# 467999_001_3_3.net
KiCad netlist of a schematic drawn in Altium Designer
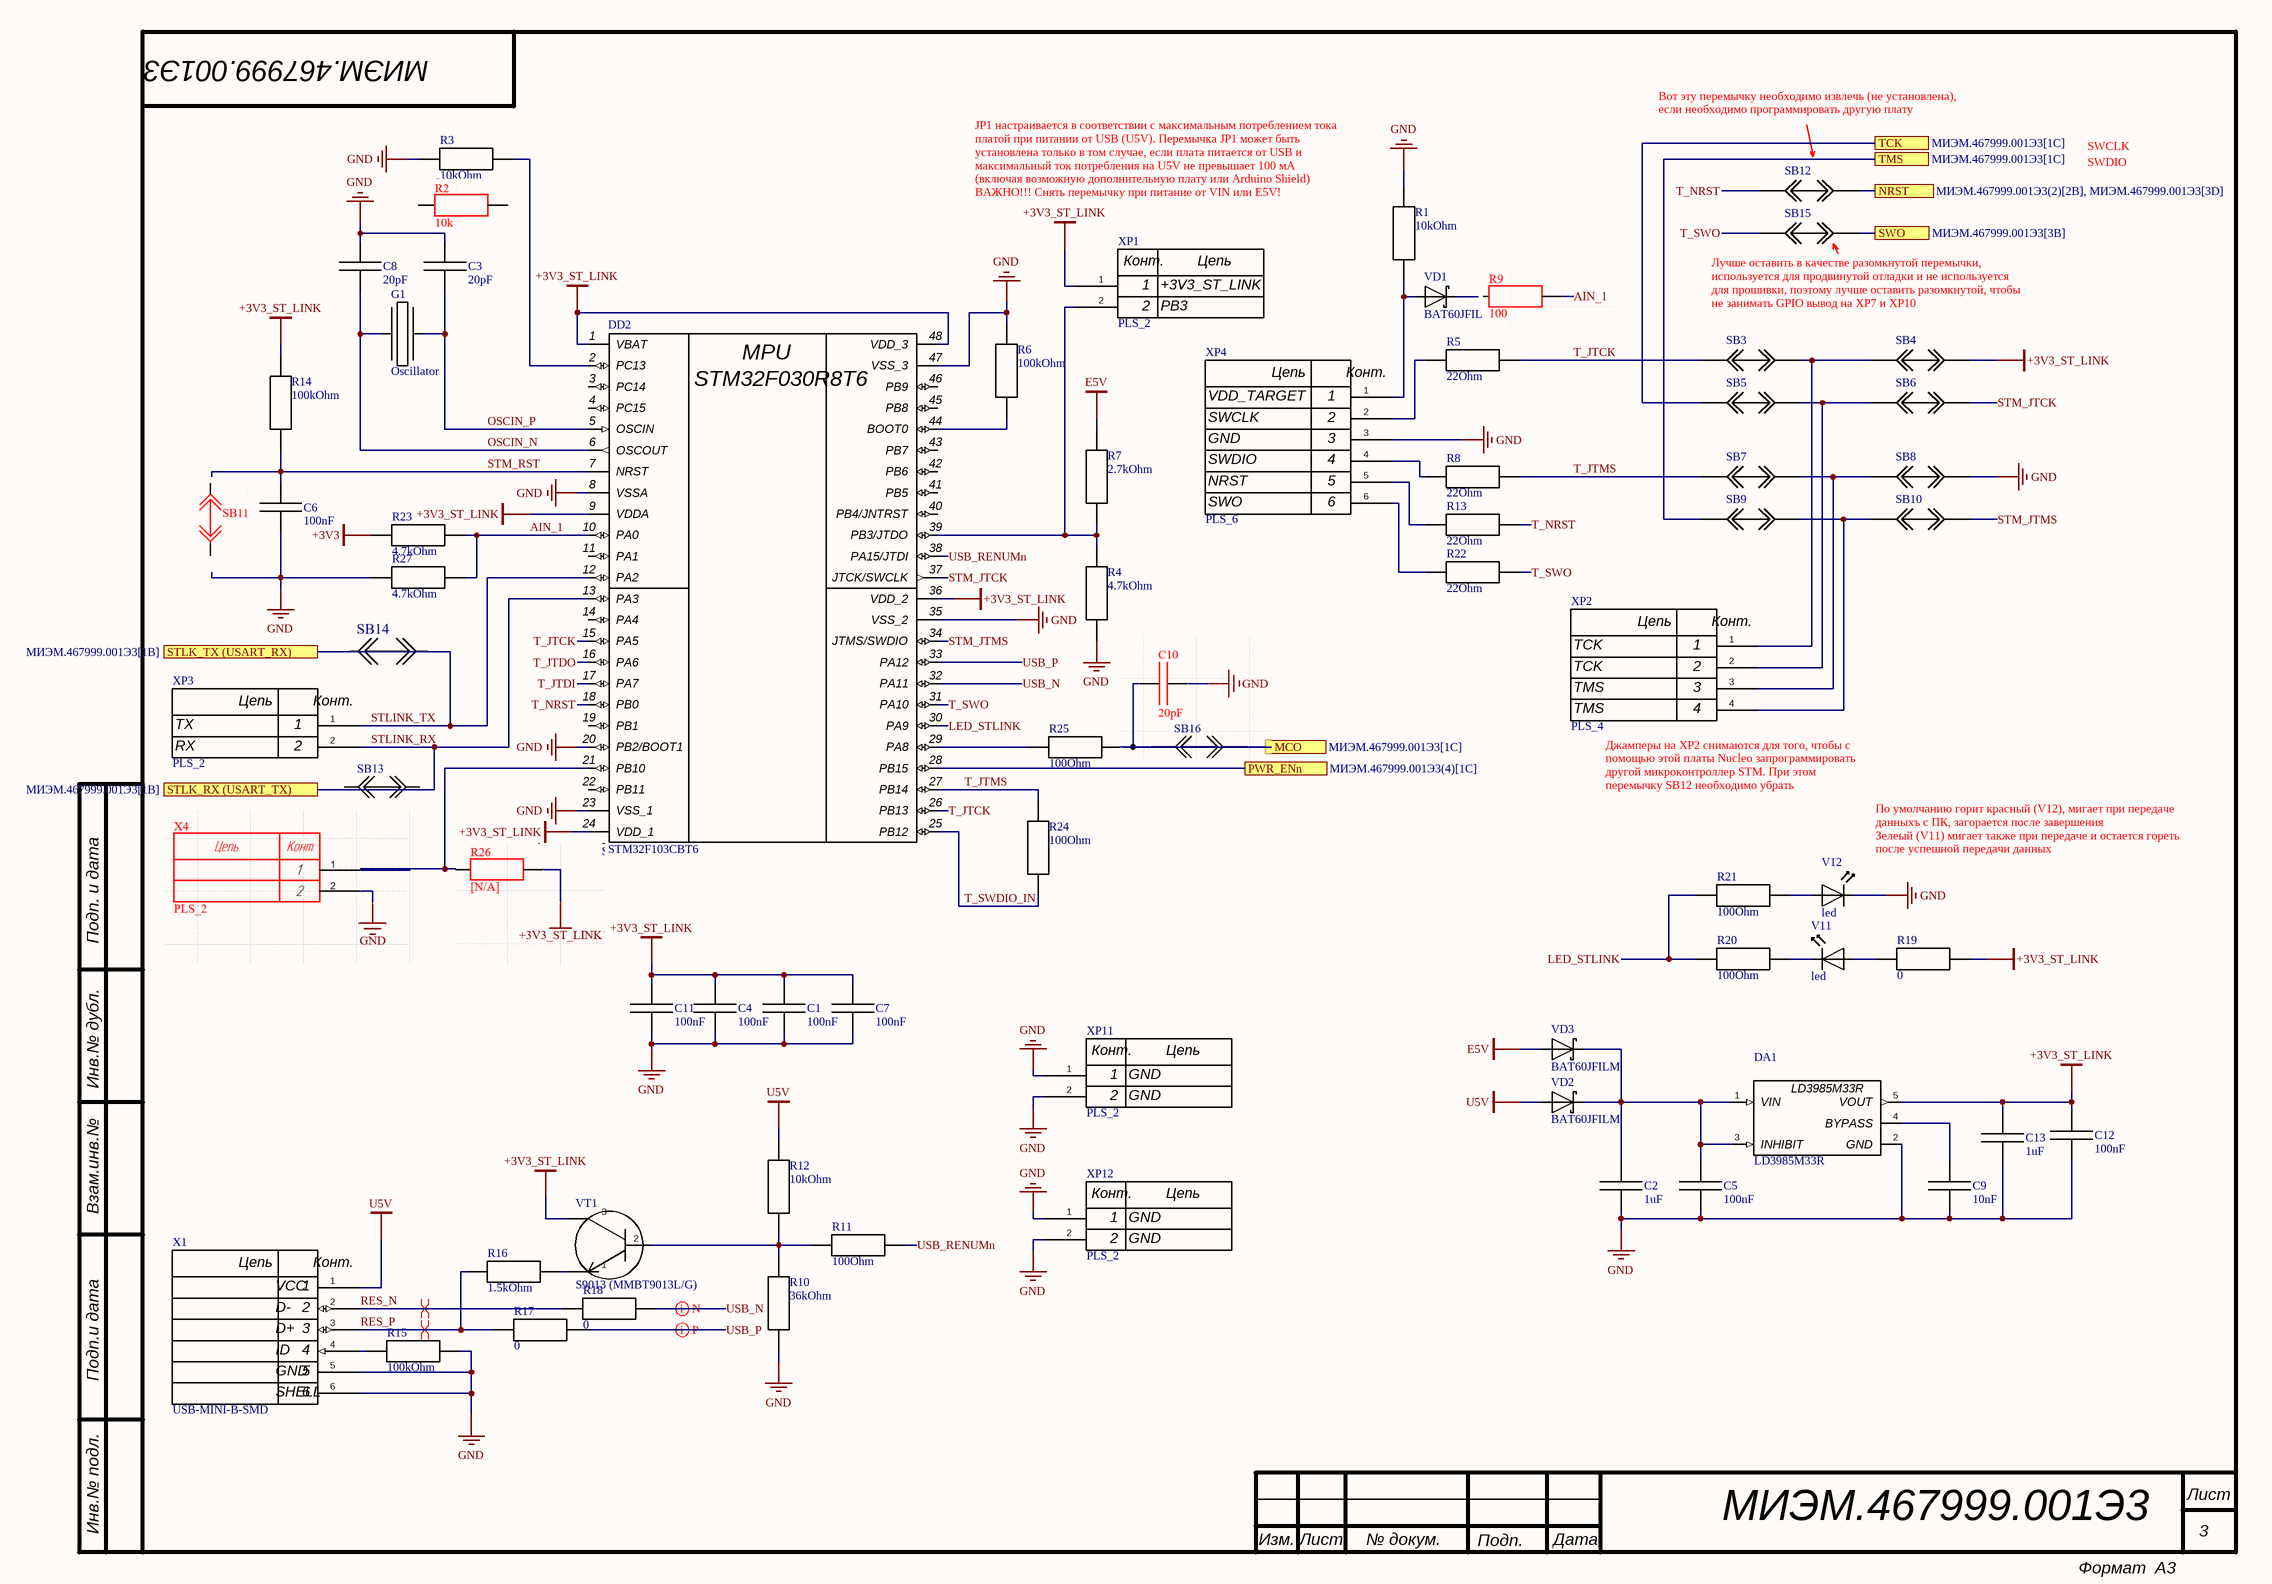
[diagram p0: МИЭМ.467999.001Э3(3).SchDoc]

(export (version "E")
  (design (tool "Eeschema 10.0.6"))
  (components
    (comp (ref "C1")
      (value "100nF")
      (footprint "0603")
      (fields
        (field (name "TOLERANCE") "10%")
        (field (name "PARTNUMBER") "CC0603KRX7R0BB104")
        (field (name "MANUFACTURER") "Yageo")
      )
      (libsource (lib "Capacitor_GOST") (part "Сapacitor"))
    )
    (comp (ref "C2")
      (value "1uF")
      (footprint "0603")
      (fields
        (field (name "TOLERANCE") "10%")
        (field (name "PARTNUMBER") "GRM185R61A105K")
        (field (name "MANUFACTURER") "Murata Electronics")
      )
      (libsource (lib "Capacitor_GOST") (part "Сapacitor"))
    )
    (comp (ref "C3")
      (value "20pF")
      (footprint "0603")
      (fields
        (field (name "TOLERANCE") "5%")
        (field (name "PARTNUMBER") "GRM1885C1H200J")
        (field (name "MANUFACTURER") "Murata Electronics")
      )
      (libsource (lib "Capacitor_GOST") (part "Сapacitor"))
    )
    (comp (ref "C4")
      (value "100nF")
      (footprint "0603")
      (fields
        (field (name "TOLERANCE") "10%")
        (field (name "PARTNUMBER") "CC0603KRX7R0BB104")
        (field (name "MANUFACTURER") "Yageo")
      )
      (libsource (lib "Capacitor_GOST") (part "Сapacitor"))
    )
    (comp (ref "C5")
      (value "100nF")
      (footprint "0603")
      (fields
        (field (name "TOLERANCE") "10%")
        (field (name "PARTNUMBER") "CC0603KRX7R0BB104")
        (field (name "MANUFACTURER") "Yageo")
      )
      (libsource (lib "Capacitor_GOST") (part "Сapacitor"))
    )
    (comp (ref "C6")
      (value "100nF")
      (footprint "0603")
      (fields
        (field (name "TOLERANCE") "10%")
        (field (name "PARTNUMBER") "CC0603KRX7R0BB104")
        (field (name "MANUFACTURER") "Yageo")
      )
      (libsource (lib "Capacitor_GOST") (part "Сapacitor"))
    )
    (comp (ref "C7")
      (value "100nF")
      (footprint "0603")
      (fields
        (field (name "TOLERANCE") "10%")
        (field (name "PARTNUMBER") "CC0603KRX7R0BB104")
        (field (name "MANUFACTURER") "Yageo")
      )
      (libsource (lib "Capacitor_GOST") (part "Сapacitor"))
    )
    (comp (ref "C8")
      (value "20pF")
      (footprint "0603")
      (fields
        (field (name "TOLERANCE") "5%")
        (field (name "PARTNUMBER") "GRM1885C1H200J")
        (field (name "MANUFACTURER") "Murata Electronics")
      )
      (libsource (lib "Capacitor_GOST") (part "Сapacitor"))
    )
    (comp (ref "C9")
      (value "10nF")
      (footprint "0603")
      (fields
        (field (name "TOLERANCE") "10%")
        (field (name "PARTNUMBER") "CC0603KRX7R0BB103")
        (field (name "MANUFACTURER") "Yageo")
      )
      (libsource (lib "Capacitor_GOST") (part "Сapacitor"))
    )
    (comp (ref "C11")
      (value "100nF")
      (footprint "0603")
      (fields
        (field (name "TOLERANCE") "10%")
        (field (name "PARTNUMBER") "CC0603KRX7R0BB104")
        (field (name "MANUFACTURER") "Yageo")
      )
      (libsource (lib "Capacitor_GOST") (part "Сapacitor"))
    )
    (comp (ref "C12")
      (value "100nF")
      (footprint "0603")
      (fields
        (field (name "TOLERANCE") "10%")
        (field (name "PARTNUMBER") "CC0603KRX7R0BB104")
        (field (name "MANUFACTURER") "Yageo")
      )
      (libsource (lib "Capacitor_GOST") (part "Сapacitor"))
    )
    (comp (ref "C13")
      (value "1uF")
      (footprint "0603")
      (fields
        (field (name "TOLERANCE") "10%")
        (field (name "PARTNUMBER") "GRM185R61A105K")
        (field (name "MANUFACTURER") "Murata Electronics")
      )
      (libsource (lib "Capacitor_GOST") (part "Сapacitor"))
    )
    (comp (ref "DA1")
      (value "LD3985M33R")
      (footprint "LD3985M33R (SOT-23-5)")
      (fields (field (name "MANUFACTURER") "STMicroelectronics"))
      (libsource (lib "ICs_GOST") (part "LD3985M33R"))
    )
    (comp (ref "DD2")
      (value "STM32F103CBT6")
      (footprint "LQFP48-7x7mm")
      (fields (field (name "MANUFACTURER") "STMicroelectronics"))
      (libsource (lib "STM_GOST") (part "STM32F103CBT6"))
    )
    (comp (ref "G1")
      (value "Oscillator")
      (footprint "HC49SMD")
      (libsource (lib "Oscillator_GOST") (part "Oscillator"))
    )
    (comp (ref "R1")
      (value "10kOhm")
      (footprint "0603")
      (fields
        (field (name "POWER") "0.1Вт")
        (field (name "TOLERANCE") "1%")
        (field (name "PARTNUMBER") "RC0603FR-0710KL")
      )
      (libsource (lib "") (part "Resistor_1"))
    )
    (comp (ref "R3")
      (value "10kOhm")
      (footprint "0603")
      (fields
        (field (name "POWER") "0.1Вт")
        (field (name "TOLERANCE") "1%")
        (field (name "PARTNUMBER") "RC0603FR-0710KL")
      )
      (libsource (lib "Resistor_GOST") (part "Resistor"))
    )
    (comp (ref "R4")
      (value "4.7kOhm")
      (footprint "0603")
      (fields
        (field (name "POWER") "0.1Вт")
        (field (name "TOLERANCE") "5%")
        (field (name "PARTNUMBER") "RC0603JR-074K7L")
      )
      (libsource (lib "") (part "Resistor_3"))
    )
    (comp (ref "R5")
      (value "22Ohm")
      (footprint "0603")
      (fields
        (field (name "POWER") "0.1Вт")
        (field (name "TOLERANCE") "1%")
        (field (name "PARTNUMBER") "RC0603FR-0722RL")
      )
      (libsource (lib "") (part "Resistor_2"))
    )
    (comp (ref "R6")
      (value "100kOhm")
      (footprint "0603")
      (fields
        (field (name "POWER") "0.1Вт")
        (field (name "TOLERANCE") "1%")
        (field (name "PARTNUMBER") "0603WAF1003T5E")
      )
      (libsource (lib "") (part "Resistor_3"))
    )
    (comp (ref "R7")
      (value "2.7kOhm")
      (footprint "0603")
      (fields
        (field (name "POWER") "0.1Вт")
        (field (name "TOLERANCE") "5%")
        (field (name "PARTNUMBER") "RC0603JR-072K7L")
      )
      (libsource (lib "") (part "Resistor_3"))
    )
    (comp (ref "R8")
      (value "22Ohm")
      (footprint "0603")
      (fields
        (field (name "POWER") "0.1Вт")
        (field (name "TOLERANCE") "1%")
        (field (name "PARTNUMBER") "RC0603FR-0722RL")
      )
      (libsource (lib "") (part "Resistor_2"))
    )
    (comp (ref "R10")
      (value "36kOhm")
      (footprint "0603")
      (fields
        (field (name "POWER") "0.1Вт")
        (field (name "TOLERANCE") "5%")
        (field (name "PARTNUMBER") "RC0603JR-0736KL")
      )
      (libsource (lib "") (part "Resistor_3"))
    )
    (comp (ref "R11")
      (value "100Ohm")
      (footprint "0603")
      (fields
        (field (name "POWER") "0.1Вт")
        (field (name "TOLERANCE") "1%")
        (field (name "PARTNUMBER") "AC0603FR-07100RL")
      )
      (libsource (lib "") (part "Resistor_2"))
    )
    (comp (ref "R12")
      (value "10kOhm")
      (footprint "0603")
      (fields
        (field (name "POWER") "0.1Вт")
        (field (name "TOLERANCE") "1%")
        (field (name "PARTNUMBER") "RC0603FR-0710KL")
      )
      (libsource (lib "") (part "Resistor_3"))
    )
    (comp (ref "R13")
      (value "22Ohm")
      (footprint "0603")
      (fields
        (field (name "POWER") "0.1Вт")
        (field (name "TOLERANCE") "1%")
        (field (name "PARTNUMBER") "RC0603FR-0722RL")
      )
      (libsource (lib "") (part "Resistor_2"))
    )
    (comp (ref "R14")
      (value "100kOhm")
      (footprint "0603")
      (fields
        (field (name "POWER") "0.1Вт")
        (field (name "TOLERANCE") "1%")
        (field (name "PARTNUMBER") "0603WAF1003T5E")
      )
      (libsource (lib "") (part "Resistor_3"))
    )
    (comp (ref "R15")
      (value "100kOhm")
      (footprint "0603")
      (fields
        (field (name "POWER") "0.1Вт")
        (field (name "TOLERANCE") "1%")
        (field (name "PARTNUMBER") "0603WAF1003T5E")
      )
      (libsource (lib "Resistor_GOST") (part "Resistor"))
    )
    (comp (ref "R16")
      (value "1.5kOhm")
      (footprint "0603")
      (fields
        (field (name "POWER") "0.1Вт")
        (field (name "TOLERANCE") "1%")
        (field (name "PARTNUMBER") "RC0603FR-071K5L")
      )
      (libsource (lib "Resistor_GOST") (part "Resistor"))
    )
    (comp (ref "R17")
      (value "0")
      (footprint "0603")
      (fields
        (field (name "POWER") "0.1Вт")
        (field (name "TOLERANCE") "1%")
        (field (name "PARTNUMBER") "RC0603FR-070RL")
      )
      (libsource (lib "Resistor_GOST") (part "Resistor"))
    )
    (comp (ref "R18")
      (value "0")
      (footprint "0603")
      (fields
        (field (name "POWER") "0.1Вт")
        (field (name "TOLERANCE") "1%")
        (field (name "PARTNUMBER") "RC0603FR-070RL")
      )
      (libsource (lib "Resistor_GOST") (part "Resistor"))
    )
    (comp (ref "R19")
      (value "0")
      (footprint "0603")
      (fields
        (field (name "POWER") "0.1Вт")
        (field (name "TOLERANCE") "1%")
        (field (name "PARTNUMBER") "RC0603FR-070RL")
      )
      (libsource (lib "Resistor_GOST") (part "Resistor"))
    )
    (comp (ref "R20")
      (value "100Ohm")
      (footprint "0603")
      (fields
        (field (name "POWER") "0.1Вт")
        (field (name "TOLERANCE") "1%")
        (field (name "PARTNUMBER") "AC0603FR-07100RL")
      )
      (libsource (lib "Resistor_GOST") (part "Resistor"))
    )
    (comp (ref "R21")
      (value "100Ohm")
      (footprint "0603")
      (fields
        (field (name "POWER") "0.1Вт")
        (field (name "TOLERANCE") "1%")
        (field (name "PARTNUMBER") "AC0603FR-07100RL")
      )
      (libsource (lib "Resistor_GOST") (part "Resistor"))
    )
    (comp (ref "R22")
      (value "22Ohm")
      (footprint "0603")
      (fields
        (field (name "POWER") "0.1Вт")
        (field (name "TOLERANCE") "1%")
        (field (name "PARTNUMBER") "RC0603FR-0722RL")
      )
      (libsource (lib "") (part "Resistor_2"))
    )
    (comp (ref "R23")
      (value "4.7kOhm")
      (footprint "0603")
      (fields
        (field (name "POWER") "0.1Вт")
        (field (name "TOLERANCE") "5%")
        (field (name "PARTNUMBER") "RC0603JR-074K7L")
      )
      (libsource (lib "Resistor_GOST") (part "Resistor"))
    )
    (comp (ref "R24")
      (value "100Ohm")
      (footprint "0603")
      (fields
        (field (name "POWER") "0.1Вт")
        (field (name "TOLERANCE") "1%")
        (field (name "PARTNUMBER") "AC0603FR-07100RL")
      )
      (libsource (lib "") (part "Resistor_3"))
    )
    (comp (ref "R25")
      (value "100Ohm")
      (footprint "0603")
      (fields
        (field (name "POWER") "0.1Вт")
        (field (name "TOLERANCE") "1%")
        (field (name "PARTNUMBER") "AC0603FR-07100RL")
      )
      (libsource (lib "") (part "Resistor_2"))
    )
    (comp (ref "R27")
      (value "4.7kOhm")
      (footprint "0603")
      (fields
        (field (name "POWER") "0.1Вт")
        (field (name "TOLERANCE") "5%")
        (field (name "PARTNUMBER") "RC0603JR-074K7L")
      )
      (libsource (lib "Resistor_GOST") (part "Resistor"))
    )
    (comp (ref "SB3")
      (value "Jumper")
      (footprint "Jumper")
      (libsource (lib "Connector_GOST") (part "Jumper"))
    )
    (comp (ref "SB4")
      (value "Jumper")
      (footprint "Jumper")
      (libsource (lib "Connector_GOST") (part "Jumper"))
    )
    (comp (ref "SB5")
      (value "Jumper")
      (footprint "Jumper")
      (libsource (lib "Connector_GOST") (part "Jumper"))
    )
    (comp (ref "SB6")
      (value "Jumper")
      (footprint "Jumper")
      (libsource (lib "Connector_GOST") (part "Jumper"))
    )
    (comp (ref "SB7")
      (value "Jumper")
      (footprint "Jumper")
      (libsource (lib "Connector_GOST") (part "Jumper"))
    )
    (comp (ref "SB8")
      (value "Jumper")
      (footprint "Jumper")
      (libsource (lib "Connector_GOST") (part "Jumper"))
    )
    (comp (ref "SB9")
      (value "Jumper")
      (footprint "Jumper")
      (libsource (lib "Connector_GOST") (part "Jumper"))
    )
    (comp (ref "SB10")
      (value "Jumper")
      (footprint "Jumper")
      (libsource (lib "Connector_GOST") (part "Jumper"))
    )
    (comp (ref "SB12")
      (value "Jumper")
      (footprint "Jumper")
      (libsource (lib "Connector_GOST") (part "Jumper"))
    )
    (comp (ref "SB15")
      (value "Jumper")
      (footprint "Jumper")
      (libsource (lib "Connector_GOST") (part "Jumper"))
    )
    (comp (ref "V11")
      (value "led")
      (footprint "FYLS-0603PGC")
      (fields
        (field (name "PARTNUMBER") "FYLS-0603PGC")
        (field (name "MANUFACTURER") "Ningbo Foryard Optoelectronics")
      )
      (libsource (lib "diodes_semiconductors_GOST") (part "led"))
    )
    (comp (ref "V12")
      (value "led")
      (footprint "FYLS-0603PGC")
      (fields
        (field (name "PARTNUMBER") "FYLS-0603PGC")
        (field (name "MANUFACTURER") "Ningbo Foryard Optoelectronics")
      )
      (libsource (lib "diodes_semiconductors_GOST") (part "led"))
    )
    (comp (ref "VD1")
      (value "BAT60JFILM")
      (footprint "BAT60JFILM")
      (fields (field (name "MANUFACTURER") "STMicroelectronics"))
      (libsource (lib "diodes_semiconductors_GOST") (part "BAT60JFILM"))
    )
    (comp (ref "VD2")
      (value "BAT60JFILM")
      (footprint "BAT60JFILM")
      (fields (field (name "MANUFACTURER") "STMicroelectronics"))
      (libsource (lib "diodes_semiconductors_GOST") (part "BAT60JFILM"))
    )
    (comp (ref "VD3")
      (value "BAT60JFILM")
      (footprint "BAT60JFILM")
      (fields (field (name "MANUFACTURER") "STMicroelectronics"))
      (libsource (lib "diodes_semiconductors_GOST") (part "BAT60JFILM"))
    )
    (comp (ref "VT1")
      (value "S9013 (MMBT9013L/G)")
      (footprint "S9013 (SOT_23_3)")
      (fields
        (field (name "POWER") "0.3Вт")
        (field (name "PARTNUMBER") "S9013")
        (field (name "MANUFACTURER") "Hottech")
      )
      (libsource (lib "diodes_semiconductors_GOST") (part "S9013 (MMBT9013L/G)"))
    )
    (comp (ref "X1")
      (value "USB-MINI-B-SMD")
      (footprint "USB-MINI-B-SMD")
      (fields (field (name "PARTNUMBER") "1734035-1"))
      (libsource (lib "Connector_GOST") (part "USB-MINI-B-SMD"))
    )
    (comp (ref "XP1") (value "PLS_2") (footprint "PLS_2") (libsource (lib "Connector_GOST") (part "PLS_2")))
    (comp (ref "XP2") (value "PLS_4") (footprint "PLS_4") (libsource (lib "Connector_GOST") (part "PLS_4")))
    (comp (ref "XP3") (value "PLS_2") (footprint "PLS_2") (libsource (lib "") (part "PLS_2_1")))
    (comp (ref "XP4") (value "PLS_6") (footprint "PLS_6") (libsource (lib "Connector_GOST") (part "PLS_6")))
    (comp (ref "XP11") (value "PLS_2") (footprint "PLS_2") (libsource (lib "Connector_GOST") (part "PLS_2")))
    (comp (ref "XP12") (value "PLS_2") (footprint "PLS_2") (libsource (lib "Connector_GOST") (part "PLS_2")))
  )
  (nets
    (net (code "1") (name "+3V3") (class "Default")
      (node (ref "R23") (pin "1") (pinfunction "1_1") (pintype "passive"))
    )
    (net (code "2") (name "+3V3_ST_LINK") (class "Default")
      (node (ref "C1") (pin "2") (pinfunction "2_2") (pintype "passive"))
      (node (ref "C11") (pin "2") (pinfunction "2_2") (pintype "passive"))
      (node (ref "C12") (pin "2") (pinfunction "2_2") (pintype "passive"))
      (node (ref "C13") (pin "2") (pinfunction "2_2") (pintype "passive"))
      (node (ref "C4") (pin "2") (pinfunction "2_2") (pintype "passive"))
      (node (ref "C7") (pin "2") (pinfunction "2_2") (pintype "passive"))
      (node (ref "DA1") (pin "5") (pinfunction "VOUT_5") (pintype "output"))
      (node (ref "DD2") (pin "1") (pinfunction "VBAT_1") (pintype "passive"))
      (node (ref "DD2") (pin "24") (pinfunction "VDD_1_24") (pintype "passive"))
      (node (ref "DD2") (pin "36") (pinfunction "VDD_2_36") (pintype "passive"))
      (node (ref "DD2") (pin "48") (pinfunction "VDD_3_48") (pintype "passive"))
      (node (ref "DD2") (pin "9") (pinfunction "VDDA_9") (pintype "passive"))
      (node (ref "R14") (pin "2") (pinfunction "2_2") (pintype "passive"))
      (node (ref "R19") (pin "2") (pinfunction "2_2") (pintype "passive"))
      (node (ref "SB4") (pin "2") (pinfunction "2_2") (pintype "passive"))
      (node (ref "VT1") (pin "3") (pinfunction "3_3") (pintype "passive"))
      (node (ref "XP1") (pin "1") (pinfunction "1_1") (pintype "passive"))
    )
    (net (code "3") (name "/AIN_1") (class "Default")
      (node (ref "DD2") (pin "10") (pinfunction "PA0_10") (pintype "bidirectional"))
      (node (ref "R23") (pin "2") (pinfunction "2_2") (pintype "passive"))
      (node (ref "R27") (pin "2") (pinfunction "2_2") (pintype "passive"))
    )
    (net (code "4") (name "/LED_STLINK") (class "Default")
      (node (ref "DD2") (pin "30") (pinfunction "PA9_30") (pintype "bidirectional"))
      (node (ref "R20") (pin "1") (pinfunction "1_1") (pintype "passive"))
      (node (ref "R21") (pin "1") (pinfunction "1_1") (pintype "passive"))
    )
    (net (code "5") (name "/MCO") (class "Default")
      (node (ref "R25") (pin "1") (pinfunction "1_1") (pintype "passive"))
    )
    (net (code "6") (name "/NRST") (class "Default")
      (node (ref "SB12") (pin "2") (pinfunction "2_2") (pintype "passive"))
    )
    (net (code "7") (name "/OSCIN_N") (class "Default")
      (node (ref "C8") (pin "1") (pinfunction "1_1") (pintype "passive"))
      (node (ref "DD2") (pin "6") (pinfunction "OSCOUT_6") (pintype "output"))
      (node (ref "G1") (pin "1") (pinfunction "1_1") (pintype "passive"))
    )
    (net (code "8") (name "/OSCIN_P") (class "Default")
      (node (ref "C3") (pin "1") (pinfunction "1_1") (pintype "passive"))
      (node (ref "DD2") (pin "5") (pinfunction "OSCIN_5") (pintype "input"))
      (node (ref "G1") (pin "2") (pinfunction "2_2") (pintype "passive"))
    )
    (net (code "9") (name "/PWR_ENn") (class "Default")
      (node (ref "DD2") (pin "28") (pinfunction "PB15_28") (pintype "bidirectional"))
    )
    (net (code "10") (name "/RES_N") (class "Default")
      (node (ref "R18") (pin "1") (pinfunction "1_1") (pintype "passive"))
      (node (ref "X1") (pin "2") (pinfunction "2_2") (pintype "bidirectional"))
    )
    (net (code "11") (name "/RES_P") (class "Default")
      (node (ref "R16") (pin "1") (pinfunction "1_1") (pintype "passive"))
      (node (ref "R17") (pin "1") (pinfunction "1_1") (pintype "passive"))
      (node (ref "X1") (pin "3") (pinfunction "3_3") (pintype "bidirectional"))
    )
    (net (code "12") (name "/STLINK_RX") (class "Default")
      (node (ref "DD2") (pin "13") (pinfunction "PA3_13") (pintype "bidirectional"))
      (node (ref "XP3") (pin "2") (pinfunction "2_2") (pintype "passive"))
    )
    (net (code "13") (name "/STLINK_TX") (class "Default")
      (node (ref "DD2") (pin "12") (pinfunction "PA2_12") (pintype "bidirectional"))
      (node (ref "XP3") (pin "1") (pinfunction "1_1") (pintype "passive"))
    )
    (net (code "14") (name "/STM_JTCK") (class "Default")
      (node (ref "DD2") (pin "37") (pinfunction "JTCK/SWCLK_37") (pintype "output"))
      (node (ref "SB6") (pin "2") (pinfunction "2_2") (pintype "passive"))
    )
    (net (code "15") (name "/STM_JTMS") (class "Default")
      (node (ref "DD2") (pin "34") (pinfunction "JTMS/SWDIO_34") (pintype "bidirectional"))
      (node (ref "SB10") (pin "2") (pinfunction "2_2") (pintype "passive"))
    )
    (net (code "16") (name "/STM_RST") (class "Default")
      (node (ref "C6") (pin "2") (pinfunction "2_2") (pintype "passive"))
      (node (ref "DD2") (pin "7") (pinfunction "NRST_7") (pintype "passive"))
      (node (ref "R14") (pin "1") (pinfunction "1_1") (pintype "passive"))
    )
    (net (code "17") (name "/SWO") (class "Default")
      (node (ref "SB15") (pin "2") (pinfunction "2_2") (pintype "passive"))
    )
    (net (code "18") (name "/TCK") (class "Default")
      (node (ref "SB5") (pin "1") (pinfunction "1_1") (pintype "passive"))
    )
    (net (code "19") (name "/TMS") (class "Default")
      (node (ref "SB9") (pin "1") (pinfunction "1_1") (pintype "passive"))
    )
    (net (code "20") (name "/T_JTCK") (class "Default")
      (node (ref "DD2") (pin "15") (pinfunction "PA5_15") (pintype "bidirectional"))
      (node (ref "DD2") (pin "26") (pinfunction "PB13_26") (pintype "bidirectional"))
      (node (ref "R5") (pin "1") (pinfunction "1_1") (pintype "passive"))
      (node (ref "SB3") (pin "1") (pinfunction "1_1") (pintype "passive"))
    )
    (net (code "21") (name "/T_JTDI") (class "Default")
      (node (ref "DD2") (pin "17") (pinfunction "PA7_17") (pintype "bidirectional"))
    )
    (net (code "22") (name "/T_JTDO") (class "Default")
      (node (ref "DD2") (pin "16") (pinfunction "PA6_16") (pintype "bidirectional"))
    )
    (net (code "23") (name "/T_JTMS") (class "Default")
      (node (ref "DD2") (pin "27") (pinfunction "PB14_27") (pintype "bidirectional"))
      (node (ref "R24") (pin "2") (pinfunction "2_2") (pintype "passive"))
      (node (ref "R8") (pin "1") (pinfunction "1_1") (pintype "passive"))
      (node (ref "SB7") (pin "1") (pinfunction "1_1") (pintype "passive"))
    )
    (net (code "24") (name "/T_NRST") (class "Default")
      (node (ref "DD2") (pin "18") (pinfunction "PB0_18") (pintype "bidirectional"))
      (node (ref "R13") (pin "1") (pinfunction "1_1") (pintype "passive"))
      (node (ref "SB12") (pin "1") (pinfunction "1_1") (pintype "passive"))
    )
    (net (code "25") (name "/T_SWDIO_IN") (class "Default")
      (node (ref "DD2") (pin "25") (pinfunction "PB12_25") (pintype "bidirectional"))
      (node (ref "R24") (pin "1") (pinfunction "1_1") (pintype "passive"))
    )
    (net (code "26") (name "/T_SWO") (class "Default")
      (node (ref "DD2") (pin "31") (pinfunction "PA10_31") (pintype "bidirectional"))
      (node (ref "R22") (pin "1") (pinfunction "1_1") (pintype "passive"))
      (node (ref "SB15") (pin "1") (pinfunction "1_1") (pintype "passive"))
    )
    (net (code "27") (name "/USB_N") (class "Default")
      (node (ref "DD2") (pin "32") (pinfunction "PA11_32") (pintype "bidirectional"))
      (node (ref "R18") (pin "2") (pinfunction "2_2") (pintype "passive"))
    )
    (net (code "28") (name "/USB_P") (class "Default")
      (node (ref "DD2") (pin "33") (pinfunction "PA12_33") (pintype "bidirectional"))
      (node (ref "R17") (pin "2") (pinfunction "2_2") (pintype "passive"))
    )
    (net (code "29") (name "/USB_RENUMn") (class "Default")
      (node (ref "DD2") (pin "38") (pinfunction "PA15/JTDI_38") (pintype "bidirectional"))
      (node (ref "R11") (pin "1") (pinfunction "1_1") (pintype "passive"))
    )
    (net (code "30") (name "E5V") (class "Default")
      (node (ref "R7") (pin "2") (pinfunction "2_2") (pintype "passive"))
      (node (ref "VD3") (pin "2") (pinfunction "2_2") (pintype "passive"))
    )
    (net (code "31") (name "GND") (class "Default")
      (node (ref "C1") (pin "1") (pinfunction "1_1") (pintype "passive"))
      (node (ref "C11") (pin "1") (pinfunction "1_1") (pintype "passive"))
      (node (ref "C12") (pin "1") (pinfunction "1_1") (pintype "passive"))
      (node (ref "C13") (pin "1") (pinfunction "1_1") (pintype "passive"))
      (node (ref "C2") (pin "1") (pinfunction "1_1") (pintype "passive"))
      (node (ref "C3") (pin "2") (pinfunction "2_2") (pintype "passive"))
      (node (ref "C4") (pin "1") (pinfunction "1_1") (pintype "passive"))
      (node (ref "C5") (pin "1") (pinfunction "1_1") (pintype "passive"))
      (node (ref "C6") (pin "1") (pinfunction "1_1") (pintype "passive"))
      (node (ref "C7") (pin "1") (pinfunction "1_1") (pintype "passive"))
      (node (ref "C8") (pin "2") (pinfunction "2_2") (pintype "passive"))
      (node (ref "C9") (pin "1") (pinfunction "1_1") (pintype "passive"))
      (node (ref "DA1") (pin "2") (pinfunction "GND_2") (pintype "passive"))
      (node (ref "DD2") (pin "20") (pinfunction "PB2/BOOT1_20") (pintype "bidirectional"))
      (node (ref "DD2") (pin "23") (pinfunction "VSS_1_23") (pintype "passive"))
      (node (ref "DD2") (pin "35") (pinfunction "VSS_2_35") (pintype "passive"))
      (node (ref "DD2") (pin "47") (pinfunction "VSS_3_47") (pintype "passive"))
      (node (ref "DD2") (pin "8") (pinfunction "VSSA_8") (pintype "passive"))
      (node (ref "R1") (pin "1") (pinfunction "1_1") (pintype "passive"))
      (node (ref "R10") (pin "1") (pinfunction "1_1") (pintype "passive"))
      (node (ref "R15") (pin "2") (pinfunction "2_2") (pintype "passive"))
      (node (ref "R27") (pin "1") (pinfunction "1_1") (pintype "passive"))
      (node (ref "R3") (pin "1") (pinfunction "1_1") (pintype "passive"))
      (node (ref "R4") (pin "1") (pinfunction "1_1") (pintype "passive"))
      (node (ref "R6") (pin "2") (pinfunction "2_2") (pintype "passive"))
      (node (ref "SB8") (pin "2") (pinfunction "2_2") (pintype "passive"))
      (node (ref "V12") (pin "2") (pinfunction "2_2") (pintype "passive"))
      (node (ref "X1") (pin "5") (pinfunction "5_5") (pintype "passive"))
      (node (ref "X1") (pin "6") (pinfunction "6_6") (pintype "passive"))
      (node (ref "XP11") (pin "1") (pinfunction "1_1") (pintype "passive"))
      (node (ref "XP11") (pin "2") (pinfunction "2_2") (pintype "passive"))
      (node (ref "XP12") (pin "1") (pinfunction "1_1") (pintype "passive"))
      (node (ref "XP12") (pin "2") (pinfunction "2_2") (pintype "passive"))
      (node (ref "XP4") (pin "3") (pinfunction "3_3") (pintype "passive"))
    )
    (net (code "32") (name "Net-(DA1-BYPASS)") (class "Default")
      (node (ref "C9") (pin "2") (pinfunction "2_2") (pintype "passive"))
      (node (ref "DA1") (pin "4") (pinfunction "BYPASS_4") (pintype "passive"))
    )
    (net (code "33") (name "Net-(DA1-INHIBIT)") (class "Default")
      (node (ref "C2") (pin "2") (pinfunction "2_2") (pintype "passive"))
      (node (ref "C5") (pin "2") (pinfunction "2_2") (pintype "passive"))
      (node (ref "DA1") (pin "1") (pinfunction "VIN_1") (pintype "input"))
      (node (ref "DA1") (pin "3") (pinfunction "INHIBIT_3") (pintype "input"))
      (node (ref "VD2") (pin "1") (pinfunction "1_1") (pintype "passive"))
      (node (ref "VD3") (pin "1") (pinfunction "1_1") (pintype "passive"))
    )
    (net (code "34") (name "Net-(DD2-BOOT0)") (class "Default")
      (node (ref "DD2") (pin "44") (pinfunction "BOOT0_44") (pintype "bidirectional"))
      (node (ref "R6") (pin "1") (pinfunction "1_1") (pintype "passive"))
    )
    (net (code "35") (name "Net-(DD2-PA8)") (class "Default")
      (node (ref "DD2") (pin "29") (pinfunction "PA8_29") (pintype "bidirectional"))
      (node (ref "R25") (pin "2") (pinfunction "2_2") (pintype "passive"))
    )
    (net (code "36") (name "Net-(DD2-PB3{slash}JTDO)") (class "Default")
      (node (ref "DD2") (pin "39") (pinfunction "PB3/JTDO_39") (pintype "bidirectional"))
      (node (ref "R4") (pin "2") (pinfunction "2_2") (pintype "passive"))
      (node (ref "R7") (pin "1") (pinfunction "1_1") (pintype "passive"))
      (node (ref "XP1") (pin "2") (pinfunction "2_2") (pintype "passive"))
    )
    (net (code "37") (name "Net-(DD2-PC13)") (class "Default")
      (node (ref "DD2") (pin "2") (pinfunction "PC13_2") (pintype "bidirectional"))
      (node (ref "R3") (pin "2") (pinfunction "2_2") (pintype "passive"))
    )
    (net (code "38") (name "Net-(R1-Pad2)") (class "Default")
      (node (ref "R1") (pin "2") (pinfunction "2_2") (pintype "passive"))
      (node (ref "VD1") (pin "2") (pinfunction "2_2") (pintype "passive"))
      (node (ref "XP4") (pin "1") (pinfunction "1_1") (pintype "passive"))
    )
    (net (code "39") (name "Net-(R5-Pad2)") (class "Default")
      (node (ref "R5") (pin "2") (pinfunction "2_2") (pintype "passive"))
      (node (ref "XP4") (pin "2") (pinfunction "2_2") (pintype "passive"))
    )
    (net (code "40") (name "Net-(R8-Pad2)") (class "Default")
      (node (ref "R8") (pin "2") (pinfunction "2_2") (pintype "passive"))
      (node (ref "XP4") (pin "4") (pinfunction "4_4") (pintype "passive"))
    )
    (net (code "41") (name "Net-(R10-Pad2)") (class "Default")
      (node (ref "R10") (pin "2") (pinfunction "2_2") (pintype "passive"))
      (node (ref "R11") (pin "2") (pinfunction "2_2") (pintype "passive"))
      (node (ref "R12") (pin "1") (pinfunction "1_1") (pintype "passive"))
      (node (ref "VT1") (pin "2") (pinfunction "2_2") (pintype "passive"))
    )
    (net (code "42") (name "Net-(R13-Pad2)") (class "Default")
      (node (ref "R13") (pin "2") (pinfunction "2_2") (pintype "passive"))
      (node (ref "XP4") (pin "5") (pinfunction "5_5") (pintype "passive"))
    )
    (net (code "43") (name "Net-(R15-Pad1)") (class "Default")
      (node (ref "R15") (pin "1") (pinfunction "1_1") (pintype "passive"))
      (node (ref "X1") (pin "4") (pinfunction "4_4") (pintype "input"))
    )
    (net (code "44") (name "Net-(R16-Pad2)") (class "Default")
      (node (ref "R16") (pin "2") (pinfunction "2_2") (pintype "passive"))
      (node (ref "VT1") (pin "1") (pinfunction "1_1") (pintype "passive"))
    )
    (net (code "45") (name "Net-(R19-Pad1)") (class "Default")
      (node (ref "R19") (pin "1") (pinfunction "1_1") (pintype "passive"))
      (node (ref "V11") (pin "1") (pinfunction "1_1") (pintype "passive"))
    )
    (net (code "46") (name "Net-(R20-Pad2)") (class "Default")
      (node (ref "R20") (pin "2") (pinfunction "2_2") (pintype "passive"))
      (node (ref "V11") (pin "2") (pinfunction "2_2") (pintype "passive"))
    )
    (net (code "47") (name "Net-(R21-Pad2)") (class "Default")
      (node (ref "R21") (pin "2") (pinfunction "2_2") (pintype "passive"))
      (node (ref "V12") (pin "1") (pinfunction "1_1") (pintype "passive"))
    )
    (net (code "48") (name "Net-(R22-Pad2)") (class "Default")
      (node (ref "R22") (pin "2") (pinfunction "2_2") (pintype "passive"))
      (node (ref "XP4") (pin "6") (pinfunction "6_6") (pintype "passive"))
    )
    (net (code "49") (name "Net-(SB3-Pad2)") (class "Default")
      (node (ref "SB3") (pin "2") (pinfunction "2_2") (pintype "passive"))
      (node (ref "SB4") (pin "1") (pinfunction "1_1") (pintype "passive"))
      (node (ref "XP2") (pin "1") (pinfunction "1_1") (pintype "passive"))
    )
    (net (code "50") (name "Net-(SB5-Pad2)") (class "Default")
      (node (ref "SB5") (pin "2") (pinfunction "2_2") (pintype "passive"))
      (node (ref "SB6") (pin "1") (pinfunction "1_1") (pintype "passive"))
      (node (ref "XP2") (pin "2") (pinfunction "2_2") (pintype "passive"))
    )
    (net (code "51") (name "Net-(SB7-Pad2)") (class "Default")
      (node (ref "SB7") (pin "2") (pinfunction "2_2") (pintype "passive"))
      (node (ref "SB8") (pin "1") (pinfunction "1_1") (pintype "passive"))
      (node (ref "XP2") (pin "3") (pinfunction "3_3") (pintype "passive"))
    )
    (net (code "52") (name "Net-(SB10-Pad1)") (class "Default")
      (node (ref "SB10") (pin "1") (pinfunction "1_1") (pintype "passive"))
      (node (ref "SB9") (pin "2") (pinfunction "2_2") (pintype "passive"))
      (node (ref "XP2") (pin "4") (pinfunction "4_4") (pintype "passive"))
    )
    (net (code "53") (name "U5V") (class "Default")
      (node (ref "R12") (pin "2") (pinfunction "2_2") (pintype "passive"))
      (node (ref "VD2") (pin "2") (pinfunction "2_2") (pintype "passive"))
      (node (ref "X1") (pin "1") (pinfunction "1_1") (pintype "passive"))
    )
    (net (code "54") (name "unconnected-(DD2-PA1-Pad11)") (class "Default")
      (node (ref "DD2") (pin "11") (pinfunction "PA1_11") (pintype "bidirectional"))
    )
    (net (code "55") (name "unconnected-(DD2-PA4-Pad14)") (class "Default")
      (node (ref "DD2") (pin "14") (pinfunction "PA4_14") (pintype "bidirectional"))
    )
    (net (code "56") (name "unconnected-(DD2-PB1-Pad19)") (class "Default")
      (node (ref "DD2") (pin "19") (pinfunction "PB1_19") (pintype "bidirectional"))
    )
    (net (code "57") (name "unconnected-(DD2-PB4{slash}JNTRST-Pad40)") (class "Default")
      (node (ref "DD2") (pin "40") (pinfunction "PB4/JNTRST_40") (pintype "bidirectional"))
    )
    (net (code "58") (name "unconnected-(DD2-PB5-Pad41)") (class "Default")
      (node (ref "DD2") (pin "41") (pinfunction "PB5_41") (pintype "bidirectional"))
    )
    (net (code "59") (name "unconnected-(DD2-PB6-Pad42)") (class "Default")
      (node (ref "DD2") (pin "42") (pinfunction "PB6_42") (pintype "bidirectional"))
    )
    (net (code "60") (name "unconnected-(DD2-PB7-Pad43)") (class "Default")
      (node (ref "DD2") (pin "43") (pinfunction "PB7_43") (pintype "bidirectional"))
    )
    (net (code "61") (name "unconnected-(DD2-PB8-Pad45)") (class "Default")
      (node (ref "DD2") (pin "45") (pinfunction "PB8_45") (pintype "bidirectional"))
    )
    (net (code "62") (name "unconnected-(DD2-PB9-Pad46)") (class "Default")
      (node (ref "DD2") (pin "46") (pinfunction "PB9_46") (pintype "bidirectional"))
    )
    (net (code "63") (name "unconnected-(DD2-PB10-Pad21)") (class "Default")
      (node (ref "DD2") (pin "21") (pinfunction "PB10_21") (pintype "bidirectional"))
    )
    (net (code "64") (name "unconnected-(DD2-PB11-Pad22)") (class "Default")
      (node (ref "DD2") (pin "22") (pinfunction "PB11_22") (pintype "bidirectional"))
    )
    (net (code "65") (name "unconnected-(DD2-PC14-Pad3)") (class "Default")
      (node (ref "DD2") (pin "3") (pinfunction "PC14_3") (pintype "bidirectional"))
    )
    (net (code "66") (name "unconnected-(DD2-PC15-Pad4)") (class "Default")
      (node (ref "DD2") (pin "4") (pinfunction "PC15_4") (pintype "bidirectional"))
    )
    (net (code "67") (name "unconnected-(VD1-Pad1)") (class "Default")
      (node (ref "VD1") (pin "1") (pinfunction "1_1") (pintype "passive"))
    )
  )
)
